# THAT_1206_Breakout.net
KiCad netlist of a schematic drawn in EAGLE
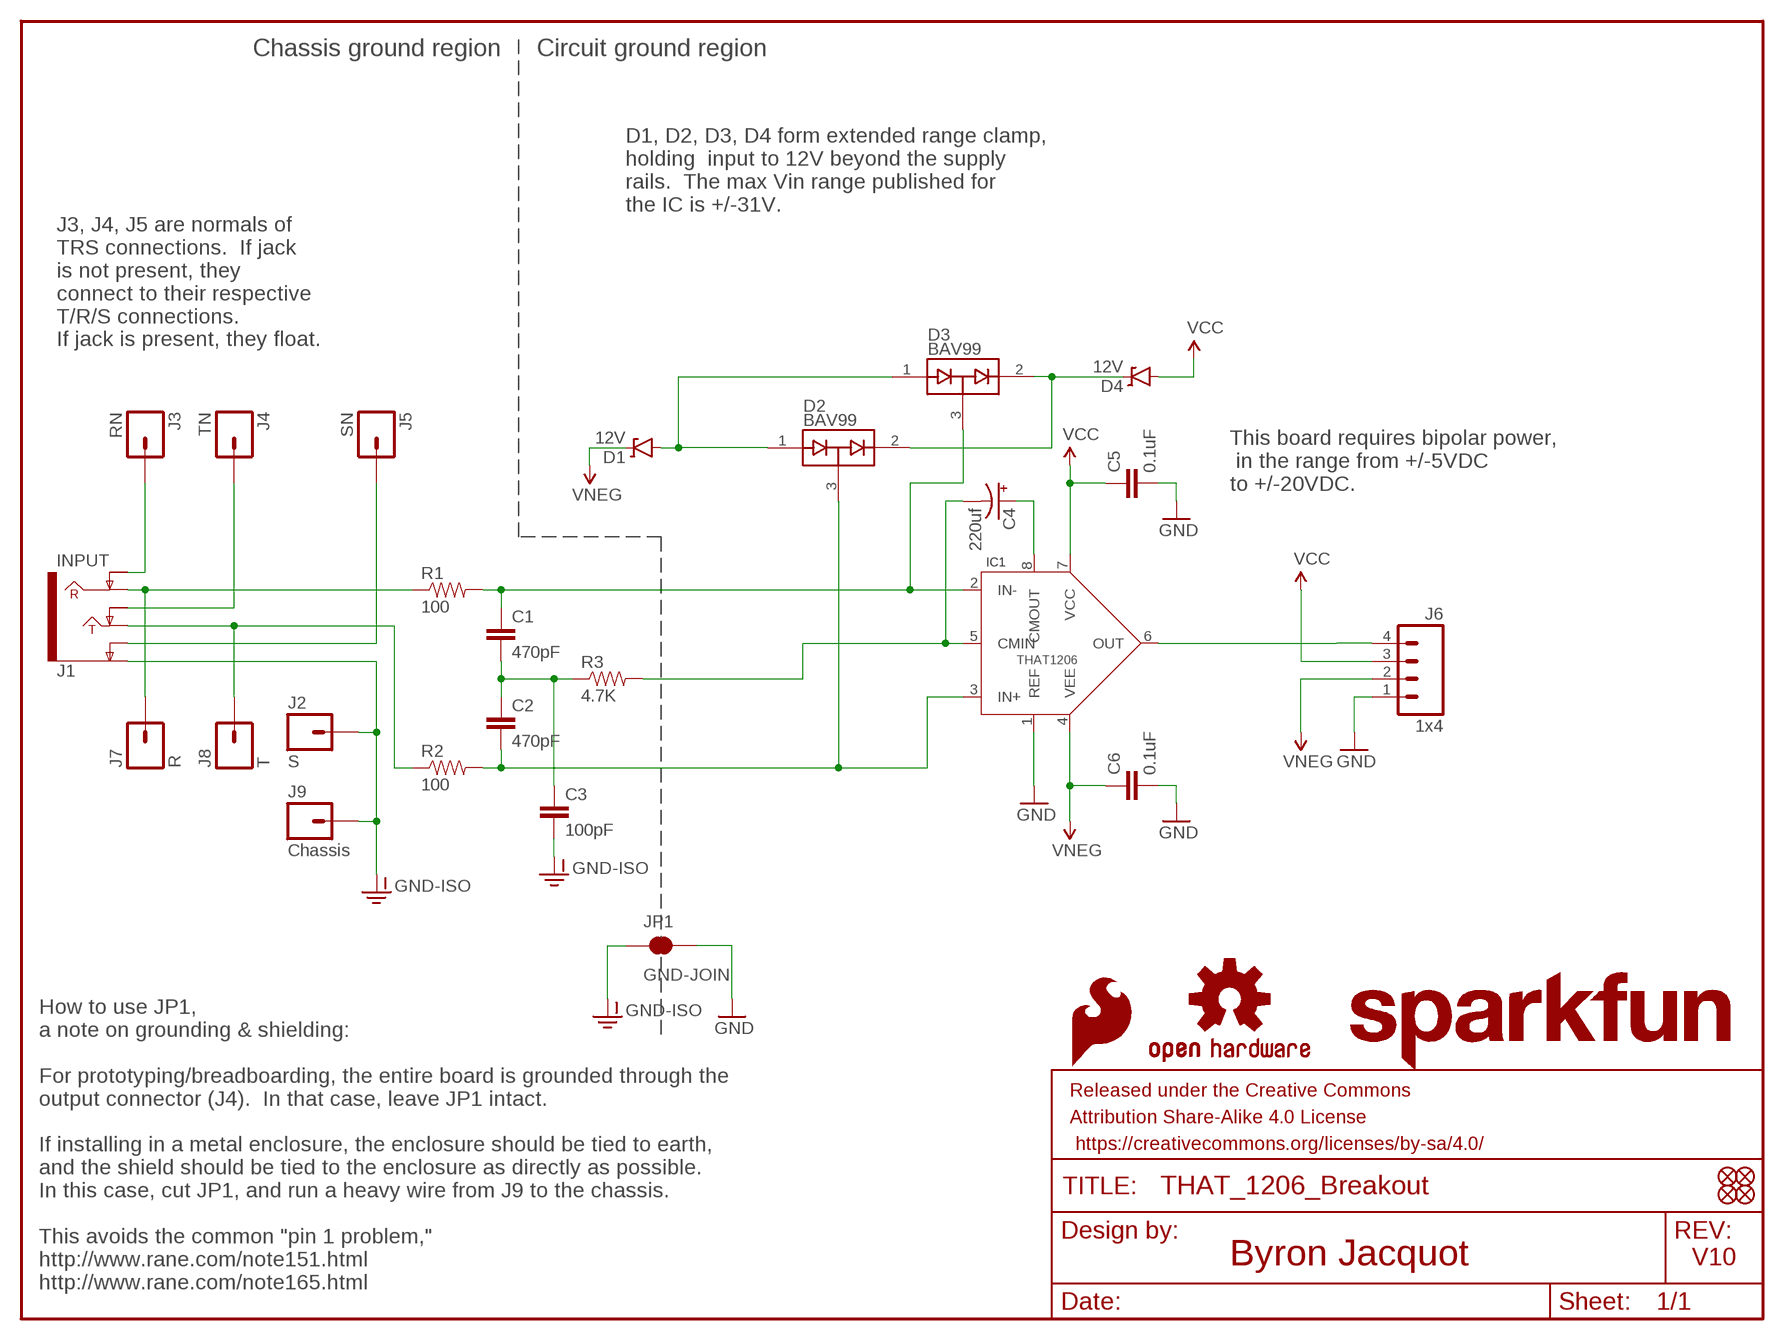
[diagram p0: schematic, sheet 1]

(export (version "E")
  (design (tool "Eeschema 10.0.6"))
  (components
    (comp (ref "C1")
      (value "470pF")
      (footprint "eagle-import:0603-CAP")
      (libsource (lib "eagle-import") (part "470PF-50V-5%(0603)SMD"))
    )
    (comp (ref "C2")
      (value "470pF")
      (footprint "eagle-import:0603-CAP")
      (libsource (lib "eagle-import") (part "470PF-50V-5%(0603)SMD"))
    )
    (comp (ref "C3")
      (value "100pF")
      (footprint "eagle-import:0603-CAP")
      (libsource (lib "eagle-import") (part "100PF-50V-5%(0603)"))
    )
    (comp (ref "C4")
      (value "220uf")
      (footprint "eagle-import:PANASONIC_D")
      (libsource (lib "eagle-import") (part "PANA-EEE-FKOJ221P"))
    )
    (comp (ref "C5")
      (value "0.1uF")
      (footprint "eagle-import:0603-CAP")
      (libsource (lib "eagle-import") (part "0.1UF-25V-5%(0603)"))
    )
    (comp (ref "C6")
      (value "0.1uF")
      (footprint "eagle-import:0603-CAP")
      (libsource (lib "eagle-import") (part "0.1UF-25V-5%(0603)"))
    )
    (comp (ref "D1")
      (value "12V")
      (footprint "eagle-import:SOD-323")
      (fields (field (name "MFR") "ON Semi"))
      (libsource (lib "eagle-import") (part "12V-ZENER-DIODE"))
    )
    (comp (ref "D2")
      (value "BAV99")
      (footprint "eagle-import:SOT23-3")
      (libsource (lib "eagle-import") (part "BAV99"))
    )
    (comp (ref "D3")
      (value "BAV99")
      (footprint "eagle-import:SOT23-3")
      (libsource (lib "eagle-import") (part "BAV99"))
    )
    (comp (ref "D4")
      (value "12V")
      (footprint "eagle-import:SOD-323")
      (fields (field (name "MFR") "ON Semi"))
      (libsource (lib "eagle-import") (part "12V-ZENER-DIODE"))
    )
    (comp (ref "FD1")
      (value "FIDUCIALUFIDUCIAL")
      (footprint "eagle-import:MICRO-FIDUCIAL")
      (libsource (lib "eagle-import") (part "FIDUCIALUFIDUCIAL"))
    )
    (comp (ref "FD2")
      (value "FIDUCIALUFIDUCIAL")
      (footprint "eagle-import:MICRO-FIDUCIAL")
      (libsource (lib "eagle-import") (part "FIDUCIALUFIDUCIAL"))
    )
    (comp (ref "FD3")
      (value "FIDUCIALUFIDUCIAL")
      (footprint "eagle-import:MICRO-FIDUCIAL")
      (libsource (lib "eagle-import") (part "FIDUCIALUFIDUCIAL"))
    )
    (comp (ref "FD4")
      (value "FIDUCIALUFIDUCIAL")
      (footprint "eagle-import:MICRO-FIDUCIAL")
      (libsource (lib "eagle-import") (part "FIDUCIALUFIDUCIAL"))
    )
    (comp (ref "FRAME1")
      (value "FRAME-LETTER")
      (footprint "eagle-import:CREATIVE_COMMONS")
      (libsource (lib "eagle-import") (part "FRAME-LETTER"))
    )
    (comp (ref "IC1")
      (value "THAT1206")
      (footprint "eagle-import:SO08")
      (libsource (lib "eagle-import") (part "THAT1206"))
    )
    (comp (ref "J1")
      (value "INPUT")
      (footprint "eagle-import:AUDIO_JACK_0.25__TRS_PTH_RA")
      (libsource (lib "eagle-import") (part "AUDIO_JACK_TRS_0.25{dblquote}_PTH_RA"))
    )
    (comp (ref "J2")
      (value "S")
      (footprint "eagle-import:1X01_NO_SILK")
      (libsource (lib "eagle-import") (part "M01PTH_NO_SILK_YES_STOP"))
    )
    (comp (ref "J3")
      (value "RN")
      (footprint "eagle-import:1X01_NO_SILK")
      (libsource (lib "eagle-import") (part "M01PTH_NO_SILK_YES_STOP"))
    )
    (comp (ref "J4")
      (value "TN")
      (footprint "eagle-import:1X01_NO_SILK")
      (libsource (lib "eagle-import") (part "M01PTH_NO_SILK_YES_STOP"))
    )
    (comp (ref "J5")
      (value "SN")
      (footprint "eagle-import:1X01_NO_SILK")
      (libsource (lib "eagle-import") (part "M01PTH_NO_SILK_YES_STOP"))
    )
    (comp (ref "J6")
      (value "1x4")
      (footprint "eagle-import:1X04_NO_SILK_ALL_ROUND")
      (libsource (lib "eagle-import") (part "M04NO_SILK_ALL_ROUND"))
    )
    (comp (ref "J7")
      (value "R")
      (footprint "eagle-import:1X01_NO_SILK")
      (libsource (lib "eagle-import") (part "M01PTH_NO_SILK_YES_STOP"))
    )
    (comp (ref "J8")
      (value "T")
      (footprint "eagle-import:1X01_NO_SILK")
      (libsource (lib "eagle-import") (part "M01PTH_NO_SILK_YES_STOP"))
    )
    (comp (ref "J9")
      (value "Chassis")
      (footprint "eagle-import:1X01_NO_SILK")
      (libsource (lib "eagle-import") (part "M01PTH_NO_SILK_YES_STOP"))
    )
    (comp (ref "JP1")
      (value "GND-JOIN")
      (footprint "eagle-import:PAD-JUMPER-2-NC_BY_TRACE_YES_SILK")
      (libsource (lib "eagle-import") (part "JUMPER-PAD-2-NC_BY_TRACE"))
    )
    (comp (ref "LOGO2")
      (value "SFE_LOGO_FLAME.2_INCH")
      (footprint "eagle-import:SFE_LOGO_FLAME_.2")
      (libsource (lib "eagle-import") (part "SFE_LOGO_FLAME.2_INCH"))
    )
    (comp (ref "LOGO3")
      (value "OSHW-LOGOS")
      (footprint "eagle-import:OSHW-LOGO-S")
      (libsource (lib "eagle-import") (part "OSHW-LOGOS"))
    )
    (comp (ref "LOGO4")
      (value "OSHW-LOGOS")
      (footprint "eagle-import:OSHW-LOGO-S")
      (libsource (lib "eagle-import") (part "OSHW-LOGOS"))
    )
    (comp (ref "LOGO5")
      (value "SFE_LOGO_NAME.1_INCH")
      (footprint "eagle-import:SFE_LOGO_NAME_.1")
      (libsource (lib "eagle-import") (part "SFE_LOGO_NAME.1_INCH"))
    )
    (comp (ref "R1")
      (value "100")
      (footprint "eagle-import:0603-RES")
      (libsource (lib "eagle-import") (part "100OHM-1/10W-1%(0603)"))
    )
    (comp (ref "R2")
      (value "100")
      (footprint "eagle-import:0603-RES")
      (libsource (lib "eagle-import") (part "100OHM-1/10W-1%(0603)"))
    )
    (comp (ref "R3")
      (value "4.7K")
      (footprint "eagle-import:0603-RES")
      (libsource (lib "eagle-import") (part "4.7KOHM-1/10W-1%(0603)"))
    )
  )
  (nets
    (net (code "1") (name "GND") (class "Default")
      (node (ref "C5") (pin "2") (pinfunction "2_2") (pintype "passive"))
      (node (ref "C6") (pin "2") (pinfunction "2_2") (pintype "passive"))
      (node (ref "IC1") (pin "1") (pinfunction "REF_1") (pintype "bidirectional"))
      (node (ref "J6") (pin "1") (pinfunction "1_1") (pintype "passive"))
      (node (ref "JP1") (pin "2") (pinfunction "2_2") (pintype "passive"))
    )
    (net (code "2") (name "GND-ISO") (class "Default")
      (node (ref "C3") (pin "2") (pinfunction "2_2") (pintype "passive"))
      (node (ref "J1") (pin "SLEEVE") (pinfunction "EARTH_SLEEVE") (pintype "bidirectional"))
      (node (ref "J2") (pin "1") (pinfunction "1_1") (pintype "passive"))
      (node (ref "J9") (pin "1") (pinfunction "1_1") (pintype "passive"))
      (node (ref "JP1") (pin "1") (pinfunction "1_1") (pintype "passive"))
    )
    (net (code "3") (name "Net-(C1-Pad2)") (class "Default")
      (node (ref "C1") (pin "2") (pinfunction "2_2") (pintype "passive"))
      (node (ref "C2") (pin "1") (pinfunction "1_1") (pintype "passive"))
      (node (ref "C3") (pin "1") (pinfunction "1_1") (pintype "passive"))
      (node (ref "R3") (pin "1") (pinfunction "1_1") (pintype "passive"))
    )
    (net (code "4") (name "Net-(D2-A1)") (class "Default")
      (node (ref "D1") (pin "A") (pinfunction "A_A") (pintype "passive"))
      (node (ref "D2") (pin "1") (pinfunction "A1_1") (pintype "bidirectional"))
      (node (ref "D3") (pin "1") (pinfunction "A1_1") (pintype "bidirectional"))
    )
    (net (code "5") (name "Net-(D2-C2)") (class "Default")
      (node (ref "D2") (pin "2") (pinfunction "C2_2") (pintype "bidirectional"))
      (node (ref "D3") (pin "2") (pinfunction "C2_2") (pintype "bidirectional"))
      (node (ref "D4") (pin "C") (pinfunction "C_C") (pintype "passive"))
    )
    (net (code "6") (name "Net-(D2-COM)") (class "Default")
      (node (ref "C2") (pin "2") (pinfunction "2_2") (pintype "passive"))
      (node (ref "D2") (pin "3") (pinfunction "COM_3") (pintype "bidirectional"))
      (node (ref "IC1") (pin "3") (pinfunction "IN+_3") (pintype "bidirectional"))
      (node (ref "R2") (pin "2") (pinfunction "2_2") (pintype "passive"))
    )
    (net (code "7") (name "Net-(D3-COM)") (class "Default")
      (node (ref "C1") (pin "1") (pinfunction "1_1") (pintype "passive"))
      (node (ref "D3") (pin "3") (pinfunction "COM_3") (pintype "bidirectional"))
      (node (ref "IC1") (pin "2") (pinfunction "IN-_2") (pintype "bidirectional"))
      (node (ref "R1") (pin "2") (pinfunction "2_2") (pintype "passive"))
    )
    (net (code "8") (name "Net-(IC1-CMIN)") (class "Default")
      (node (ref "C4") (pin "-") (pinfunction "-_-") (pintype "passive"))
      (node (ref "IC1") (pin "5") (pinfunction "CMIN_5") (pintype "bidirectional"))
      (node (ref "R3") (pin "2") (pinfunction "2_2") (pintype "passive"))
    )
    (net (code "9") (name "Net-(IC1-CMOUT)") (class "Default")
      (node (ref "C4") (pin "+") (pinfunction "+_+") (pintype "passive"))
      (node (ref "IC1") (pin "8") (pinfunction "CMOUT_8") (pintype "bidirectional"))
    )
    (net (code "10") (name "Net-(IC1-OUT)") (class "Default")
      (node (ref "IC1") (pin "6") (pinfunction "OUT_6") (pintype "bidirectional"))
      (node (ref "J6") (pin "4") (pinfunction "4_4") (pintype "passive"))
    )
    (net (code "11") (name "Net-(J1-EARTH-NORM)") (class "Default")
      (node (ref "J1") (pin "SLEEVE-NORM") (pinfunction "EARTH-NORM_SLEEVE-NORM") (pintype "bidirectional"))
      (node (ref "J5") (pin "1") (pinfunction "1_1") (pintype "passive"))
    )
    (net (code "12") (name "Net-(J1-PadRING)") (class "Default")
      (node (ref "J1") (pin "RING") (pinfunction "RING_RING") (pintype "bidirectional"))
      (node (ref "J7") (pin "1") (pinfunction "1_1") (pintype "passive"))
      (node (ref "R1") (pin "1") (pinfunction "1_1") (pintype "passive"))
    )
    (net (code "13") (name "Net-(J1-PadRING-NORM)") (class "Default")
      (node (ref "J1") (pin "RING-NORM") (pinfunction "RING-NORM_RING-NORM") (pintype "bidirectional"))
      (node (ref "J3") (pin "1") (pinfunction "1_1") (pintype "passive"))
    )
    (net (code "14") (name "Net-(J1-PadTIP)") (class "Default")
      (node (ref "J1") (pin "TIP") (pinfunction "TIP_TIP") (pintype "bidirectional"))
      (node (ref "J8") (pin "1") (pinfunction "1_1") (pintype "passive"))
      (node (ref "R2") (pin "1") (pinfunction "1_1") (pintype "passive"))
    )
    (net (code "15") (name "Net-(J1-PadTIP-NORM)") (class "Default")
      (node (ref "J1") (pin "TIP-NORM") (pinfunction "TIP-NORM_TIP-NORM") (pintype "bidirectional"))
      (node (ref "J4") (pin "1") (pinfunction "1_1") (pintype "passive"))
    )
    (net (code "16") (name "VCC") (class "Default")
      (node (ref "C5") (pin "1") (pinfunction "1_1") (pintype "passive"))
      (node (ref "D4") (pin "A") (pinfunction "A_A") (pintype "passive"))
      (node (ref "IC1") (pin "7") (pinfunction "VCC_7") (pintype "bidirectional"))
      (node (ref "J6") (pin "3") (pinfunction "3_3") (pintype "passive"))
    )
    (net (code "17") (name "VNEG") (class "Default")
      (node (ref "C6") (pin "1") (pinfunction "1_1") (pintype "passive"))
      (node (ref "D1") (pin "C") (pinfunction "C_C") (pintype "passive"))
      (node (ref "IC1") (pin "4") (pinfunction "VEE_4") (pintype "bidirectional"))
      (node (ref "J6") (pin "2") (pinfunction "2_2") (pintype "passive"))
    )
  )
)
